# TPA3116AudioAmplifier.net
KiCad netlist of a schematic drawn in EAGLE
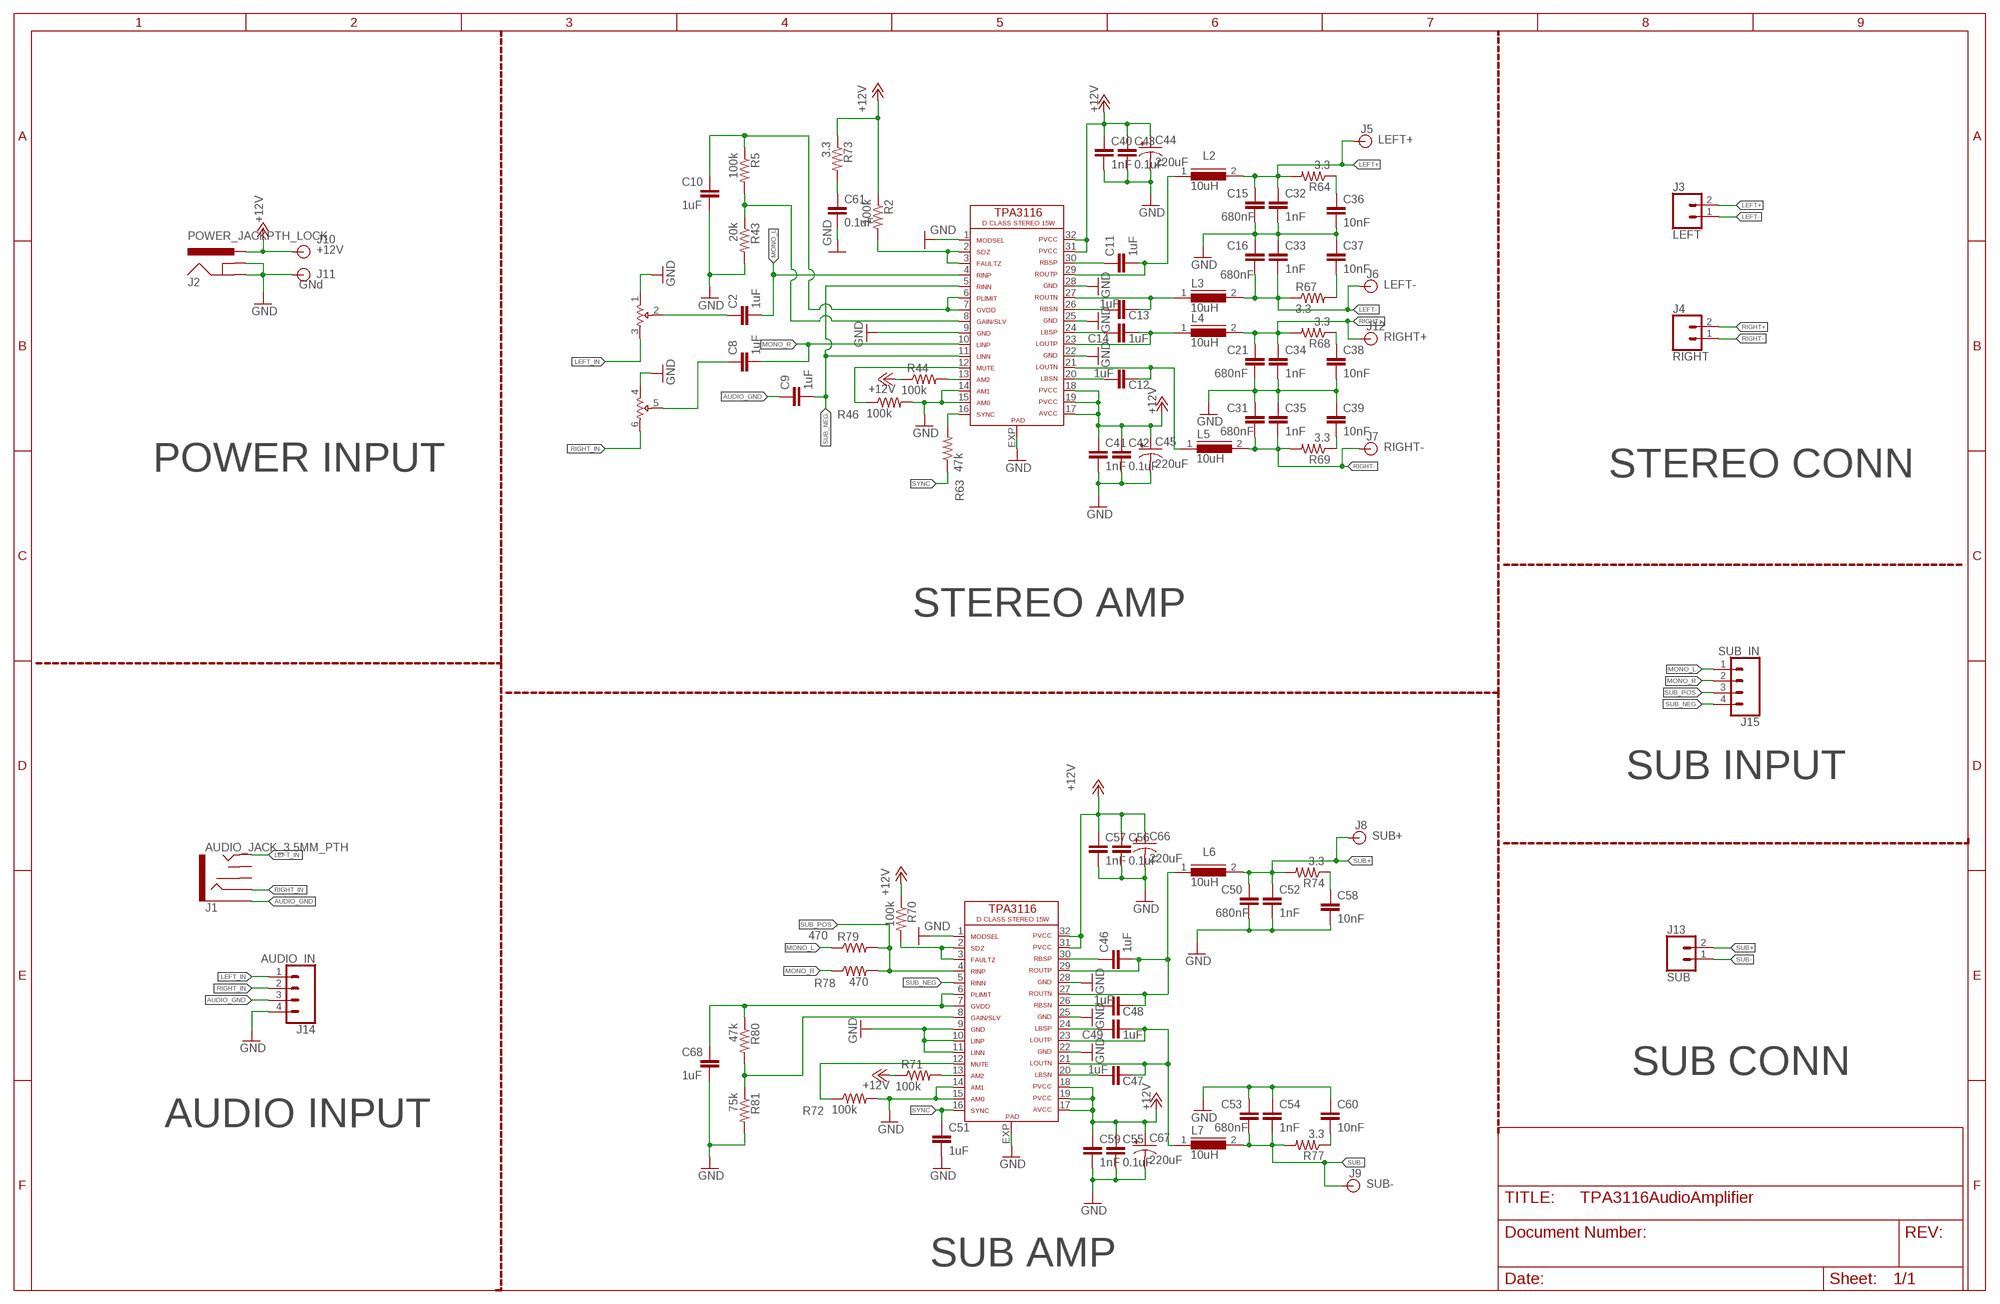
[diagram p0: schematic, sheet 1]

(export (version "E")
  (design (tool "Eeschema 10.0.6"))
  (components
    (comp (ref "C2")
      (value "1uF")
      (footprint "eagle-import:C0603K")
      (libsource (lib "eagle-import") (part "C-EUC0603K"))
    )
    (comp (ref "C8")
      (value "1uF")
      (footprint "eagle-import:C0603K")
      (libsource (lib "eagle-import") (part "C-EUC0603K"))
    )
    (comp (ref "C9")
      (value "1uF")
      (footprint "eagle-import:C0603K")
      (libsource (lib "eagle-import") (part "C-EUC0603K"))
    )
    (comp (ref "C10")
      (value "1uF")
      (footprint "eagle-import:C0603K")
      (libsource (lib "eagle-import") (part "C-EUC0603K"))
    )
    (comp (ref "C11")
      (value "1uF")
      (footprint "eagle-import:C0603K")
      (libsource (lib "eagle-import") (part "C-EUC0603K"))
    )
    (comp (ref "C12")
      (value "1uF")
      (footprint "eagle-import:C0603K")
      (libsource (lib "eagle-import") (part "C-EUC0603K"))
    )
    (comp (ref "C13")
      (value "1uF")
      (footprint "eagle-import:C0603K")
      (libsource (lib "eagle-import") (part "C-EUC0603K"))
    )
    (comp (ref "C14")
      (value "1uF")
      (footprint "eagle-import:C0603K")
      (libsource (lib "eagle-import") (part "C-EUC0603K"))
    )
    (comp (ref "C15")
      (value "680nF")
      (footprint "eagle-import:C0805")
      (libsource (lib "eagle-import") (part "C-EUC0805"))
    )
    (comp (ref "C16")
      (value "680nF")
      (footprint "eagle-import:C0805")
      (libsource (lib "eagle-import") (part "C-EUC0805"))
    )
    (comp (ref "C21")
      (value "680nF")
      (footprint "eagle-import:C0805")
      (libsource (lib "eagle-import") (part "C-EUC0805"))
    )
    (comp (ref "C31")
      (value "680nF")
      (footprint "eagle-import:C0805")
      (libsource (lib "eagle-import") (part "C-EUC0805"))
    )
    (comp (ref "C32")
      (value "1nF")
      (footprint "eagle-import:C0603K")
      (libsource (lib "eagle-import") (part "C-EUC0603K"))
    )
    (comp (ref "C33")
      (value "1nF")
      (footprint "eagle-import:C0603K")
      (libsource (lib "eagle-import") (part "C-EUC0603K"))
    )
    (comp (ref "C34")
      (value "1nF")
      (footprint "eagle-import:C0603K")
      (libsource (lib "eagle-import") (part "C-EUC0603K"))
    )
    (comp (ref "C35")
      (value "1nF")
      (footprint "eagle-import:C0603K")
      (libsource (lib "eagle-import") (part "C-EUC0603K"))
    )
    (comp (ref "C36")
      (value "10nF")
      (footprint "eagle-import:C0603K")
      (libsource (lib "eagle-import") (part "C-EUC0603K"))
    )
    (comp (ref "C37")
      (value "10nF")
      (footprint "eagle-import:C0603K")
      (libsource (lib "eagle-import") (part "C-EUC0603K"))
    )
    (comp (ref "C38")
      (value "10nF")
      (footprint "eagle-import:C0603K")
      (libsource (lib "eagle-import") (part "C-EUC0603K"))
    )
    (comp (ref "C39")
      (value "10nF")
      (footprint "eagle-import:C0603K")
      (libsource (lib "eagle-import") (part "C-EUC0603K"))
    )
    (comp (ref "C40")
      (value "1nF")
      (footprint "eagle-import:C0603K")
      (libsource (lib "eagle-import") (part "C-EUC0603K"))
    )
    (comp (ref "C41")
      (value "1nF")
      (footprint "eagle-import:C0603K")
      (libsource (lib "eagle-import") (part "C-EUC0603K"))
    )
    (comp (ref "C42")
      (value "0.1uF")
      (footprint "eagle-import:C0603K")
      (libsource (lib "eagle-import") (part "C-EUC0603K"))
    )
    (comp (ref "C43")
      (value "0.1uF")
      (footprint "eagle-import:C0603K")
      (libsource (lib "eagle-import") (part "C-EUC0603K"))
    )
    (comp (ref "C44")
      (value "220uF")
      (footprint "eagle-import:E5-10,5")
      (libsource (lib "eagle-import") (part "CPOL-USE5-10.5"))
    )
    (comp (ref "C45")
      (value "220uF")
      (footprint "eagle-import:E5-10,5")
      (libsource (lib "eagle-import") (part "CPOL-USE5-10.5"))
    )
    (comp (ref "C46")
      (value "1uF")
      (footprint "eagle-import:C0603K")
      (libsource (lib "eagle-import") (part "C-EUC0603K"))
    )
    (comp (ref "C47")
      (value "1uF")
      (footprint "eagle-import:C0603K")
      (libsource (lib "eagle-import") (part "C-EUC0603K"))
    )
    (comp (ref "C48")
      (value "1uF")
      (footprint "eagle-import:C0603K")
      (libsource (lib "eagle-import") (part "C-EUC0603K"))
    )
    (comp (ref "C49")
      (value "1uF")
      (footprint "eagle-import:C0603K")
      (libsource (lib "eagle-import") (part "C-EUC0603K"))
    )
    (comp (ref "C50")
      (value "680nF")
      (footprint "eagle-import:C0805")
      (libsource (lib "eagle-import") (part "C-EUC0805"))
    )
    (comp (ref "C51")
      (value "1uF")
      (footprint "eagle-import:C0603K")
      (libsource (lib "eagle-import") (part "C-EUC0603K"))
    )
    (comp (ref "C52")
      (value "1nF")
      (footprint "eagle-import:C0603K")
      (libsource (lib "eagle-import") (part "C-EUC0603K"))
    )
    (comp (ref "C53")
      (value "680nF")
      (footprint "eagle-import:C0805")
      (libsource (lib "eagle-import") (part "C-EUC0805"))
    )
    (comp (ref "C54")
      (value "1nF")
      (footprint "eagle-import:C0603K")
      (libsource (lib "eagle-import") (part "C-EUC0603K"))
    )
    (comp (ref "C55")
      (value "0.1uF")
      (footprint "eagle-import:C0603K")
      (libsource (lib "eagle-import") (part "C-EUC0603K"))
    )
    (comp (ref "C56")
      (value "0.1uF")
      (footprint "eagle-import:C0603K")
      (libsource (lib "eagle-import") (part "C-EUC0603K"))
    )
    (comp (ref "C57")
      (value "1nF")
      (footprint "eagle-import:C0603K")
      (libsource (lib "eagle-import") (part "C-EUC0603K"))
    )
    (comp (ref "C58")
      (value "10nF")
      (footprint "eagle-import:C0603K")
      (libsource (lib "eagle-import") (part "C-EUC0603K"))
    )
    (comp (ref "C59")
      (value "1nF")
      (footprint "eagle-import:C0603K")
      (libsource (lib "eagle-import") (part "C-EUC0603K"))
    )
    (comp (ref "C60")
      (value "10nF")
      (footprint "eagle-import:C0603K")
      (libsource (lib "eagle-import") (part "C-EUC0603K"))
    )
    (comp (ref "C61")
      (value "0.1uF")
      (footprint "eagle-import:C0603K")
      (libsource (lib "eagle-import") (part "C-EUC0603K"))
    )
    (comp (ref "C66")
      (value "220uF")
      (footprint "eagle-import:E5-10,5")
      (libsource (lib "eagle-import") (part "CPOL-USE5-10.5"))
    )
    (comp (ref "C67")
      (value "220uF")
      (footprint "eagle-import:E5-10,5")
      (libsource (lib "eagle-import") (part "CPOL-USE5-10.5"))
    )
    (comp (ref "C68")
      (value "1uF")
      (footprint "eagle-import:C0603K")
      (libsource (lib "eagle-import") (part "C-EUC0603K"))
    )
    (comp (ref "J1")
      (value "AUDIO_JACK_3.5MM_PTH")
      (footprint "eagle-import:AUDIO-JACK")
      (libsource (lib "eagle-import") (part "AUDIO_JACK_3.5MM_PTH"))
    )
    (comp (ref "J2")
      (value "POWER_JACKPTH_LOCK")
      (footprint "eagle-import:POWER_JACK_PTH_LOCK")
      (libsource (lib "eagle-import") (part "POWER_JACKPTH_LOCK"))
    )
    (comp (ref "J3")
      (value "LEFT")
      (footprint "eagle-import:SCREWTERMINAL-5MM-2")
      (libsource (lib "eagle-import") (part "CONN_025MM"))
    )
    (comp (ref "J4")
      (value "RIGHT")
      (footprint "eagle-import:SCREWTERMINAL-5MM-2")
      (libsource (lib "eagle-import") (part "CONN_025MM"))
    )
    (comp (ref "J5")
      (value "LEFT+")
      (footprint "eagle-import:BANANA_CONN")
      (libsource (lib "eagle-import") (part "BANANA_CONN"))
    )
    (comp (ref "J6")
      (value "LEFT-")
      (footprint "eagle-import:BANANA_CONN")
      (libsource (lib "eagle-import") (part "BANANA_CONN"))
    )
    (comp (ref "J7")
      (value "RIGHT-")
      (footprint "eagle-import:BANANA_CONN")
      (libsource (lib "eagle-import") (part "BANANA_CONN"))
    )
    (comp (ref "J8")
      (value "SUB+")
      (footprint "eagle-import:BANANA_CONN")
      (libsource (lib "eagle-import") (part "BANANA_CONN"))
    )
    (comp (ref "J9")
      (value "SUB-")
      (footprint "eagle-import:BANANA_CONN")
      (libsource (lib "eagle-import") (part "BANANA_CONN"))
    )
    (comp (ref "J10")
      (value "+12V")
      (footprint "eagle-import:BANANA_CONN")
      (libsource (lib "eagle-import") (part "BANANA_CONN"))
    )
    (comp (ref "J11")
      (value "GNd")
      (footprint "eagle-import:BANANA_CONN")
      (libsource (lib "eagle-import") (part "BANANA_CONN"))
    )
    (comp (ref "J12")
      (value "RIGHT+")
      (footprint "eagle-import:BANANA_CONN")
      (libsource (lib "eagle-import") (part "BANANA_CONN"))
    )
    (comp (ref "J13")
      (value "SUB")
      (footprint "eagle-import:SCREWTERMINAL-5MM-2")
      (libsource (lib "eagle-import") (part "CONN_025MM"))
    )
    (comp (ref "J14")
      (value "AUDIO_IN")
      (footprint "eagle-import:1X04")
      (libsource (lib "eagle-import") (part "CONN_04"))
    )
    (comp (ref "J15")
      (value "SUB_IN")
      (footprint "eagle-import:1X04")
      (libsource (lib "eagle-import") (part "CONN_04"))
    )
    (comp (ref "L2")
      (value "10uH")
      (footprint "eagle-import:DR125")
      (libsource (lib "eagle-import") (part "DR125"))
    )
    (comp (ref "L3")
      (value "10uH")
      (footprint "eagle-import:DR125")
      (libsource (lib "eagle-import") (part "DR125"))
    )
    (comp (ref "L4")
      (value "10uH")
      (footprint "eagle-import:DR125")
      (libsource (lib "eagle-import") (part "DR125"))
    )
    (comp (ref "L5")
      (value "10uH")
      (footprint "eagle-import:DR125")
      (libsource (lib "eagle-import") (part "DR125"))
    )
    (comp (ref "L6")
      (value "10uH")
      (footprint "eagle-import:DR125")
      (libsource (lib "eagle-import") (part "DR125"))
    )
    (comp (ref "L7")
      (value "10uH")
      (footprint "eagle-import:DR125")
      (libsource (lib "eagle-import") (part "DR125"))
    )
    (comp (ref "R2")
      (value "100k")
      (footprint "eagle-import:R0805")
      (libsource (lib "eagle-import") (part "R-US_R0805"))
    )
    (comp (ref "R5")
      (value "100k")
      (footprint "eagle-import:R0805")
      (libsource (lib "eagle-import") (part "R-US_R0805"))
    )
    (comp (ref "R43")
      (value "20k")
      (footprint "eagle-import:R0805")
      (libsource (lib "eagle-import") (part "R-US_R0805"))
    )
    (comp (ref "R44")
      (value "100k")
      (footprint "eagle-import:R0805")
      (libsource (lib "eagle-import") (part "R-US_R0805"))
    )
    (comp (ref "R46")
      (value "100k")
      (footprint "eagle-import:R0805")
      (libsource (lib "eagle-import") (part "R-US_R0805"))
    )
    (comp (ref "R63")
      (value "47k")
      (footprint "eagle-import:R0805")
      (libsource (lib "eagle-import") (part "R-US_R0805"))
    )
    (comp (ref "R64")
      (value "3.3")
      (footprint "eagle-import:M0805")
      (libsource (lib "eagle-import") (part "R-US_M0805"))
    )
    (comp (ref "R67")
      (value "3.3")
      (footprint "eagle-import:M0805")
      (libsource (lib "eagle-import") (part "R-US_M0805"))
    )
    (comp (ref "R68")
      (value "3.3")
      (footprint "eagle-import:M0805")
      (libsource (lib "eagle-import") (part "R-US_M0805"))
    )
    (comp (ref "R69")
      (value "3.3")
      (footprint "eagle-import:M0805")
      (libsource (lib "eagle-import") (part "R-US_M0805"))
    )
    (comp (ref "R70")
      (value "100k")
      (footprint "eagle-import:R0805")
      (libsource (lib "eagle-import") (part "R-US_R0805"))
    )
    (comp (ref "R71")
      (value "100k")
      (footprint "eagle-import:R0805")
      (libsource (lib "eagle-import") (part "R-US_R0805"))
    )
    (comp (ref "R72")
      (value "100k")
      (footprint "eagle-import:R0805")
      (libsource (lib "eagle-import") (part "R-US_R0805"))
    )
    (comp (ref "R73")
      (value "3.3")
      (footprint "eagle-import:M0805")
      (libsource (lib "eagle-import") (part "R-US_M0805"))
    )
    (comp (ref "R74")
      (value "3.3")
      (footprint "eagle-import:M0805")
      (libsource (lib "eagle-import") (part "R-US_M0805"))
    )
    (comp (ref "R77")
      (value "3.3")
      (footprint "eagle-import:M0805")
      (libsource (lib "eagle-import") (part "R-US_M0805"))
    )
    (comp (ref "R78")
      (value "470")
      (footprint "eagle-import:R0805")
      (libsource (lib "eagle-import") (part "R-US_R0805"))
    )
    (comp (ref "R79")
      (value "470")
      (footprint "eagle-import:R0805")
      (libsource (lib "eagle-import") (part "R-US_R0805"))
    )
    (comp (ref "R80")
      (value "47k")
      (footprint "eagle-import:R0805")
      (libsource (lib "eagle-import") (part "R-US_R0805"))
    )
    (comp (ref "R81")
      (value "75k")
      (footprint "eagle-import:R0805")
      (libsource (lib "eagle-import") (part "R-US_R0805"))
    )
    (comp (ref "U$1")
      (value "TPA3116HTSSOP32")
      (footprint "eagle-import:HTSSOP32DAP")
      (libsource (lib "eagle-import") (part "TPA3116HTSSOP32"))
    )
    (comp (ref "U$2")
      (value "DUAL_POT_H")
      (footprint "eagle-import:DUAL_POT_H")
      (libsource (lib "eagle-import") (part "DUAL_POT_H"))
    )
    (comp (ref "U$3")
      (value "TPA3116HTSSOP32")
      (footprint "eagle-import:HTSSOP32DAP")
      (libsource (lib "eagle-import") (part "TPA3116HTSSOP32"))
    )
  )
  (nets
    (net (code "1") (name "+12V") (class "Default")
      (node (ref "C40") (pin "1") (pinfunction "1_1") (pintype "passive"))
      (node (ref "C41") (pin "1") (pinfunction "1_1") (pintype "passive"))
      (node (ref "C42") (pin "1") (pinfunction "1_1") (pintype "passive"))
      (node (ref "C43") (pin "1") (pinfunction "1_1") (pintype "passive"))
      (node (ref "C44") (pin "+") (pinfunction "+_+") (pintype "passive"))
      (node (ref "C45") (pin "+") (pinfunction "+_+") (pintype "passive"))
      (node (ref "C55") (pin "1") (pinfunction "1_1") (pintype "passive"))
      (node (ref "C56") (pin "1") (pinfunction "1_1") (pintype "passive"))
      (node (ref "C57") (pin "1") (pinfunction "1_1") (pintype "passive"))
      (node (ref "C59") (pin "1") (pinfunction "1_1") (pintype "passive"))
      (node (ref "C66") (pin "+") (pinfunction "+_+") (pintype "passive"))
      (node (ref "C67") (pin "+") (pinfunction "+_+") (pintype "passive"))
      (node (ref "J10") (pin "P$1") (pinfunction "1_P$1") (pintype "passive"))
      (node (ref "J2") (pin "PWR") (pinfunction "PWR_PWR") (pintype "bidirectional"))
      (node (ref "R2") (pin "1") (pinfunction "1_1") (pintype "passive"))
      (node (ref "R44") (pin "1") (pinfunction "1_1") (pintype "passive"))
      (node (ref "R70") (pin "1") (pinfunction "1_1") (pintype "passive"))
      (node (ref "R71") (pin "1") (pinfunction "1_1") (pintype "passive"))
      (node (ref "R73") (pin "1") (pinfunction "1_1") (pintype "passive"))
      (node (ref "U$1") (pin "17") (pinfunction "AVCC_17") (pintype "bidirectional"))
      (node (ref "U$1") (pin "18") (pinfunction "PVCC0_18") (pintype "bidirectional"))
      (node (ref "U$1") (pin "19") (pinfunction "PVCC1_19") (pintype "bidirectional"))
      (node (ref "U$1") (pin "31") (pinfunction "PVCC2_31") (pintype "bidirectional"))
      (node (ref "U$1") (pin "32") (pinfunction "PVCC3_32") (pintype "bidirectional"))
      (node (ref "U$3") (pin "17") (pinfunction "AVCC_17") (pintype "bidirectional"))
      (node (ref "U$3") (pin "18") (pinfunction "PVCC0_18") (pintype "bidirectional"))
      (node (ref "U$3") (pin "19") (pinfunction "PVCC1_19") (pintype "bidirectional"))
      (node (ref "U$3") (pin "31") (pinfunction "PVCC2_31") (pintype "bidirectional"))
      (node (ref "U$3") (pin "32") (pinfunction "PVCC3_32") (pintype "bidirectional"))
    )
    (net (code "2") (name "AUDIO_GND") (class "Default")
      (node (ref "C9") (pin "1") (pinfunction "1_1") (pintype "passive"))
      (node (ref "J1") (pin "SLEEVE") (pinfunction "SLEEVE_SLEEVE") (pintype "bidirectional"))
      (node (ref "J14") (pin "3") (pinfunction "3_3") (pintype "passive"))
    )
    (net (code "3") (name "GND") (class "Default")
      (node (ref "C10") (pin "2") (pinfunction "2_2") (pintype "passive"))
      (node (ref "C15") (pin "2") (pinfunction "2_2") (pintype "passive"))
      (node (ref "C16") (pin "1") (pinfunction "1_1") (pintype "passive"))
      (node (ref "C21") (pin "2") (pinfunction "2_2") (pintype "passive"))
      (node (ref "C31") (pin "1") (pinfunction "1_1") (pintype "passive"))
      (node (ref "C32") (pin "2") (pinfunction "2_2") (pintype "passive"))
      (node (ref "C33") (pin "1") (pinfunction "1_1") (pintype "passive"))
      (node (ref "C34") (pin "2") (pinfunction "2_2") (pintype "passive"))
      (node (ref "C35") (pin "1") (pinfunction "1_1") (pintype "passive"))
      (node (ref "C36") (pin "2") (pinfunction "2_2") (pintype "passive"))
      (node (ref "C37") (pin "1") (pinfunction "1_1") (pintype "passive"))
      (node (ref "C38") (pin "2") (pinfunction "2_2") (pintype "passive"))
      (node (ref "C39") (pin "1") (pinfunction "1_1") (pintype "passive"))
      (node (ref "C40") (pin "2") (pinfunction "2_2") (pintype "passive"))
      (node (ref "C41") (pin "2") (pinfunction "2_2") (pintype "passive"))
      (node (ref "C42") (pin "2") (pinfunction "2_2") (pintype "passive"))
      (node (ref "C43") (pin "2") (pinfunction "2_2") (pintype "passive"))
      (node (ref "C44") (pin "-") (pinfunction "-_-") (pintype "passive"))
      (node (ref "C45") (pin "-") (pinfunction "-_-") (pintype "passive"))
      (node (ref "C50") (pin "2") (pinfunction "2_2") (pintype "passive"))
      (node (ref "C51") (pin "2") (pinfunction "2_2") (pintype "passive"))
      (node (ref "C52") (pin "2") (pinfunction "2_2") (pintype "passive"))
      (node (ref "C53") (pin "1") (pinfunction "1_1") (pintype "passive"))
      (node (ref "C54") (pin "1") (pinfunction "1_1") (pintype "passive"))
      (node (ref "C55") (pin "2") (pinfunction "2_2") (pintype "passive"))
      (node (ref "C56") (pin "2") (pinfunction "2_2") (pintype "passive"))
      (node (ref "C57") (pin "2") (pinfunction "2_2") (pintype "passive"))
      (node (ref "C58") (pin "2") (pinfunction "2_2") (pintype "passive"))
      (node (ref "C59") (pin "2") (pinfunction "2_2") (pintype "passive"))
      (node (ref "C60") (pin "1") (pinfunction "1_1") (pintype "passive"))
      (node (ref "C61") (pin "2") (pinfunction "2_2") (pintype "passive"))
      (node (ref "C66") (pin "-") (pinfunction "-_-") (pintype "passive"))
      (node (ref "C67") (pin "-") (pinfunction "-_-") (pintype "passive"))
      (node (ref "C68") (pin "2") (pinfunction "2_2") (pintype "passive"))
      (node (ref "J11") (pin "P$1") (pinfunction "1_P$1") (pintype "passive"))
      (node (ref "J14") (pin "4") (pinfunction "4_4") (pintype "passive"))
      (node (ref "J2") (pin "GND") (pinfunction "GND_GND") (pintype "bidirectional"))
      (node (ref "J2") (pin "GNDBREAK") (pinfunction "GNDBREAK_GNDBREAK") (pintype "bidirectional"))
      (node (ref "R43") (pin "2") (pinfunction "2_2") (pintype "passive"))
      (node (ref "R46") (pin "2") (pinfunction "2_2") (pintype "passive"))
      (node (ref "R72") (pin "2") (pinfunction "2_2") (pintype "passive"))
      (node (ref "R81") (pin "2") (pinfunction "2_2") (pintype "passive"))
      (node (ref "U$1") (pin "1") (pinfunction "MODSEL_1") (pintype "bidirectional"))
      (node (ref "U$1") (pin "10") (pinfunction "LINP_10") (pintype "bidirectional"))
      (node (ref "U$1") (pin "11") (pinfunction "LINN_11") (pintype "bidirectional"))
      (node (ref "U$1") (pin "14") (pinfunction "AM1_14") (pintype "bidirectional"))
      (node (ref "U$1") (pin "15") (pinfunction "AM0_15") (pintype "bidirectional"))
      (node (ref "U$1") (pin "22") (pinfunction "GND1_22") (pintype "bidirectional"))
      (node (ref "U$1") (pin "25") (pinfunction "GND2_25") (pintype "bidirectional"))
      (node (ref "U$1") (pin "28") (pinfunction "GND3_28") (pintype "bidirectional"))
      (node (ref "U$1") (pin "9") (pinfunction "GND0_9") (pintype "bidirectional"))
      (node (ref "U$1") (pin "EXP") (pinfunction "EXP_EXP") (pintype "bidirectional"))
      (node (ref "U$2") (pin "1") (pinfunction "1_1") (pintype "bidirectional"))
      (node (ref "U$2") (pin "4") (pinfunction "4_4") (pintype "bidirectional"))
      (node (ref "U$3") (pin "1") (pinfunction "MODSEL_1") (pintype "bidirectional"))
      (node (ref "U$3") (pin "14") (pinfunction "AM1_14") (pintype "bidirectional"))
      (node (ref "U$3") (pin "15") (pinfunction "AM0_15") (pintype "bidirectional"))
      (node (ref "U$3") (pin "22") (pinfunction "GND1_22") (pintype "bidirectional"))
      (node (ref "U$3") (pin "25") (pinfunction "GND2_25") (pintype "bidirectional"))
      (node (ref "U$3") (pin "28") (pinfunction "GND3_28") (pintype "bidirectional"))
      (node (ref "U$3") (pin "9") (pinfunction "GND0_9") (pintype "bidirectional"))
      (node (ref "U$3") (pin "EXP") (pinfunction "EXP_EXP") (pintype "bidirectional"))
    )
    (net (code "4") (name "LEFT+") (class "Default")
      (node (ref "C15") (pin "1") (pinfunction "1_1") (pintype "passive"))
      (node (ref "C32") (pin "1") (pinfunction "1_1") (pintype "passive"))
      (node (ref "J3") (pin "2") (pinfunction "2_2") (pintype "passive"))
      (node (ref "J5") (pin "P$1") (pinfunction "1_P$1") (pintype "passive"))
      (node (ref "L2") (pin "2") (pinfunction "2_2") (pintype "passive"))
      (node (ref "R64") (pin "2") (pinfunction "2_2") (pintype "passive"))
    )
    (net (code "5") (name "LEFT-") (class "Default")
      (node (ref "C16") (pin "2") (pinfunction "2_2") (pintype "passive"))
      (node (ref "C33") (pin "2") (pinfunction "2_2") (pintype "passive"))
      (node (ref "J3") (pin "1") (pinfunction "1_1") (pintype "passive"))
      (node (ref "J6") (pin "P$1") (pinfunction "1_P$1") (pintype "passive"))
      (node (ref "L3") (pin "2") (pinfunction "2_2") (pintype "passive"))
      (node (ref "R67") (pin "1") (pinfunction "1_1") (pintype "passive"))
    )
    (net (code "6") (name "LEFT_IN") (class "Default")
      (node (ref "J1") (pin "TIP") (pinfunction "TIP_TIP") (pintype "bidirectional"))
      (node (ref "J14") (pin "1") (pinfunction "1_1") (pintype "passive"))
      (node (ref "U$2") (pin "3") (pinfunction "3_3") (pintype "bidirectional"))
    )
    (net (code "7") (name "MONO_L") (class "Default")
      (node (ref "C2") (pin "2") (pinfunction "2_2") (pintype "passive"))
      (node (ref "J15") (pin "1") (pinfunction "1_1") (pintype "passive"))
      (node (ref "R79") (pin "1") (pinfunction "1_1") (pintype "passive"))
      (node (ref "U$3") (pin "4") (pinfunction "RINP_4") (pintype "bidirectional"))
    )
    (net (code "8") (name "MONO_R") (class "Default")
      (node (ref "C8") (pin "2") (pinfunction "2_2") (pintype "passive"))
      (node (ref "J15") (pin "2") (pinfunction "2_2") (pintype "passive"))
      (node (ref "R78") (pin "1") (pinfunction "1_1") (pintype "passive"))
      (node (ref "U$3") (pin "10") (pinfunction "LINP_10") (pintype "bidirectional"))
    )
    (net (code "9") (name "Net-(C2-Pad1)") (class "Default")
      (node (ref "C2") (pin "1") (pinfunction "1_1") (pintype "passive"))
      (node (ref "U$2") (pin "2") (pinfunction "2_2") (pintype "bidirectional"))
    )
    (net (code "10") (name "Net-(C8-Pad1)") (class "Default")
      (node (ref "C8") (pin "1") (pinfunction "1_1") (pintype "passive"))
      (node (ref "U$2") (pin "5") (pinfunction "5_5") (pintype "bidirectional"))
    )
    (net (code "11") (name "Net-(C36-Pad1)") (class "Default")
      (node (ref "C36") (pin "1") (pinfunction "1_1") (pintype "passive"))
      (node (ref "R64") (pin "1") (pinfunction "1_1") (pintype "passive"))
    )
    (net (code "12") (name "Net-(C37-Pad2)") (class "Default")
      (node (ref "C37") (pin "2") (pinfunction "2_2") (pintype "passive"))
      (node (ref "R67") (pin "2") (pinfunction "2_2") (pintype "passive"))
    )
    (net (code "13") (name "Net-(C38-Pad1)") (class "Default")
      (node (ref "C38") (pin "1") (pinfunction "1_1") (pintype "passive"))
      (node (ref "R68") (pin "1") (pinfunction "1_1") (pintype "passive"))
    )
    (net (code "14") (name "Net-(C39-Pad2)") (class "Default")
      (node (ref "C39") (pin "2") (pinfunction "2_2") (pintype "passive"))
      (node (ref "R69") (pin "1") (pinfunction "1_1") (pintype "passive"))
    )
    (net (code "15") (name "Net-(C58-Pad1)") (class "Default")
      (node (ref "C58") (pin "1") (pinfunction "1_1") (pintype "passive"))
      (node (ref "R74") (pin "1") (pinfunction "1_1") (pintype "passive"))
    )
    (net (code "16") (name "Net-(C60-Pad2)") (class "Default")
      (node (ref "C60") (pin "2") (pinfunction "2_2") (pintype "passive"))
      (node (ref "R77") (pin "1") (pinfunction "1_1") (pintype "passive"))
    )
    (net (code "17") (name "Net-(C61-Pad1)") (class "Default")
      (node (ref "C61") (pin "1") (pinfunction "1_1") (pintype "passive"))
      (node (ref "R73") (pin "2") (pinfunction "2_2") (pintype "passive"))
    )
    (net (code "18") (name "Net-(U$1-AM2)") (class "Default")
      (node (ref "R71") (pin "2") (pinfunction "2_2") (pintype "passive"))
      (node (ref "U$1") (pin "13") (pinfunction "AM2_13") (pintype "bidirectional"))
    )
    (net (code "19") (name "Net-(U$1-FAULTZ)") (class "Default")
      (node (ref "R70") (pin "2") (pinfunction "2_2") (pintype "passive"))
      (node (ref "U$1") (pin "2") (pinfunction "SDZ_2") (pintype "bidirectional"))
      (node (ref "U$1") (pin "3") (pinfunction "FAULTZ_3") (pintype "bidirectional"))
    )
    (net (code "20") (name "Net-(U$1-GAIN{slash}SLV)") (class "Default")
      (node (ref "R80") (pin "2") (pinfunction "2_2") (pintype "passive"))
      (node (ref "R81") (pin "1") (pinfunction "1_1") (pintype "passive"))
      (node (ref "U$1") (pin "8") (pinfunction "GAIN/SLV_8") (pintype "bidirectional"))
    )
    (net (code "21") (name "Net-(U$1-GVDD)") (class "Default")
      (node (ref "C68") (pin "1") (pinfunction "1_1") (pintype "passive"))
      (node (ref "R80") (pin "1") (pinfunction "1_1") (pintype "passive"))
      (node (ref "U$1") (pin "6") (pinfunction "PLIMIT_6") (pintype "bidirectional"))
      (node (ref "U$1") (pin "7") (pinfunction "GVDD_7") (pintype "bidirectional"))
    )
    (net (code "22") (name "Net-(U$1-LBSN)") (class "Default")
      (node (ref "C47") (pin "1") (pinfunction "1_1") (pintype "passive"))
      (node (ref "U$1") (pin "20") (pinfunction "LBSN_20") (pintype "bidirectional"))
    )
    (net (code "23") (name "Net-(U$1-LBSP)") (class "Default")
      (node (ref "C49") (pin "1") (pinfunction "1_1") (pintype "passive"))
      (node (ref "U$1") (pin "24") (pinfunction "LBSP_24") (pintype "bidirectional"))
    )
    (net (code "24") (name "Net-(U$1-LOUTN)") (class "Default")
      (node (ref "C47") (pin "2") (pinfunction "2_2") (pintype "passive"))
      (node (ref "C49") (pin "2") (pinfunction "2_2") (pintype "passive"))
      (node (ref "L7") (pin "1") (pinfunction "1_1") (pintype "passive"))
      (node (ref "U$1") (pin "21") (pinfunction "LOUTN_21") (pintype "bidirectional"))
      (node (ref "U$1") (pin "23") (pinfunction "OUTPL_23") (pintype "bidirectional"))
    )
    (net (code "25") (name "Net-(U$1-MUTE)") (class "Default")
      (node (ref "R72") (pin "1") (pinfunction "1_1") (pintype "passive"))
      (node (ref "U$1") (pin "12") (pinfunction "MUTE_12") (pintype "bidirectional"))
    )
    (net (code "26") (name "Net-(U$1-RBSN)") (class "Default")
      (node (ref "C48") (pin "1") (pinfunction "1_1") (pintype "passive"))
      (node (ref "U$1") (pin "26") (pinfunction "RBSN_26") (pintype "bidirectional"))
    )
    (net (code "27") (name "Net-(U$1-RBSP)") (class "Default")
      (node (ref "C46") (pin "1") (pinfunction "1_1") (pintype "passive"))
      (node (ref "U$1") (pin "30") (pinfunction "RBSP_30") (pintype "bidirectional"))
    )
    (net (code "28") (name "Net-(U$1-ROUTN)") (class "Default")
      (node (ref "C46") (pin "2") (pinfunction "2_2") (pintype "passive"))
      (node (ref "C48") (pin "2") (pinfunction "2_2") (pintype "passive"))
      (node (ref "L6") (pin "1") (pinfunction "1_1") (pintype "passive"))
      (node (ref "U$1") (pin "27") (pinfunction "ROUTN_27") (pintype "bidirectional"))
      (node (ref "U$1") (pin "29") (pinfunction "ROUTP_29") (pintype "bidirectional"))
    )
    (net (code "29") (name "Net-(U$3-AM2)") (class "Default")
      (node (ref "R44") (pin "2") (pinfunction "2_2") (pintype "passive"))
      (node (ref "U$3") (pin "13") (pinfunction "AM2_13") (pintype "bidirectional"))
    )
    (net (code "30") (name "Net-(U$3-FAULTZ)") (class "Default")
      (node (ref "R2") (pin "2") (pinfunction "2_2") (pintype "passive"))
      (node (ref "U$3") (pin "2") (pinfunction "SDZ_2") (pintype "bidirectional"))
      (node (ref "U$3") (pin "3") (pinfunction "FAULTZ_3") (pintype "bidirectional"))
    )
    (net (code "31") (name "Net-(U$3-GAIN{slash}SLV)") (class "Default")
      (node (ref "R43") (pin "1") (pinfunction "1_1") (pintype "passive"))
      (node (ref "R5") (pin "2") (pinfunction "2_2") (pintype "passive"))
      (node (ref "U$3") (pin "8") (pinfunction "GAIN/SLV_8") (pintype "bidirectional"))
    )
    (net (code "32") (name "Net-(U$3-GVDD)") (class "Default")
      (node (ref "C10") (pin "1") (pinfunction "1_1") (pintype "passive"))
      (node (ref "R5") (pin "1") (pinfunction "1_1") (pintype "passive"))
      (node (ref "U$3") (pin "6") (pinfunction "PLIMIT_6") (pintype "bidirectional"))
      (node (ref "U$3") (pin "7") (pinfunction "GVDD_7") (pintype "bidirectional"))
    )
    (net (code "33") (name "Net-(U$3-LBSN)") (class "Default")
      (node (ref "C12") (pin "1") (pinfunction "1_1") (pintype "passive"))
      (node (ref "U$3") (pin "20") (pinfunction "LBSN_20") (pintype "bidirectional"))
    )
    (net (code "34") (name "Net-(U$3-LBSP)") (class "Default")
      (node (ref "C14") (pin "1") (pinfunction "1_1") (pintype "passive"))
      (node (ref "U$3") (pin "24") (pinfunction "LBSP_24") (pintype "bidirectional"))
    )
    (net (code "35") (name "Net-(U$3-LOUTN)") (class "Default")
      (node (ref "C12") (pin "2") (pinfunction "2_2") (pintype "passive"))
      (node (ref "L5") (pin "1") (pinfunction "1_1") (pintype "passive"))
      (node (ref "U$3") (pin "21") (pinfunction "LOUTN_21") (pintype "bidirectional"))
    )
    (net (code "36") (name "Net-(U$3-MUTE)") (class "Default")
      (node (ref "R46") (pin "1") (pinfunction "1_1") (pintype "passive"))
      (node (ref "U$3") (pin "12") (pinfunction "MUTE_12") (pintype "bidirectional"))
    )
    (net (code "37") (name "Net-(U$3-OUTPL)") (class "Default")
      (node (ref "C14") (pin "2") (pinfunction "2_2") (pintype "passive"))
      (node (ref "L4") (pin "1") (pinfunction "1_1") (pintype "passive"))
      (node (ref "U$3") (pin "23") (pinfunction "OUTPL_23") (pintype "bidirectional"))
    )
    (net (code "38") (name "Net-(U$3-RBSN)") (class "Default")
      (node (ref "C13") (pin "1") (pinfunction "1_1") (pintype "passive"))
      (node (ref "U$3") (pin "26") (pinfunction "RBSN_26") (pintype "bidirectional"))
    )
    (net (code "39") (name "Net-(U$3-RBSP)") (class "Default")
      (node (ref "C11") (pin "1") (pinfunction "1_1") (pintype "passive"))
      (node (ref "U$3") (pin "30") (pinfunction "RBSP_30") (pintype "bidirectional"))
    )
    (net (code "40") (name "Net-(U$3-ROUTN)") (class "Default")
      (node (ref "C13") (pin "2") (pinfunction "2_2") (pintype "passive"))
      (node (ref "L3") (pin "1") (pinfunction "1_1") (pintype "passive"))
      (node (ref "U$3") (pin "27") (pinfunction "ROUTN_27") (pintype "bidirectional"))
    )
    (net (code "41") (name "Net-(U$3-ROUTP)") (class "Default")
      (node (ref "C11") (pin "2") (pinfunction "2_2") (pintype "passive"))
      (node (ref "L2") (pin "1") (pinfunction "1_1") (pintype "passive"))
      (node (ref "U$3") (pin "29") (pinfunction "ROUTP_29") (pintype "bidirectional"))
    )
    (net (code "42") (name "Net-(U$3-SYNC)") (class "Default")
      (node (ref "R63") (pin "2") (pinfunction "2_2") (pintype "passive"))
      (node (ref "U$3") (pin "16") (pinfunction "SYNC_16") (pintype "bidirectional"))
    )
    (net (code "43") (name "RIGHT+") (class "Default")
      (node (ref "C21") (pin "1") (pinfunction "1_1") (pintype "passive"))
      (node (ref "C34") (pin "1") (pinfunction "1_1") (pintype "passive"))
      (node (ref "J12") (pin "P$1") (pinfunction "1_P$1") (pintype "passive"))
      (node (ref "J4") (pin "2") (pinfunction "2_2") (pintype "passive"))
      (node (ref "L4") (pin "2") (pinfunction "2_2") (pintype "passive"))
      (node (ref "R68") (pin "2") (pinfunction "2_2") (pintype "passive"))
    )
    (net (code "44") (name "RIGHT-") (class "Default")
      (node (ref "C31") (pin "2") (pinfunction "2_2") (pintype "passive"))
      (node (ref "C35") (pin "2") (pinfunction "2_2") (pintype "passive"))
      (node (ref "J4") (pin "1") (pinfunction "1_1") (pintype "passive"))
      (node (ref "J7") (pin "P$1") (pinfunction "1_P$1") (pintype "passive"))
      (node (ref "L5") (pin "2") (pinfunction "2_2") (pintype "passive"))
      (node (ref "R69") (pin "2") (pinfunction "2_2") (pintype "passive"))
    )
    (net (code "45") (name "RIGHT_IN") (class "Default")
      (node (ref "J1") (pin "RING") (pinfunction "RING_RING") (pintype "bidirectional"))
      (node (ref "J14") (pin "2") (pinfunction "2_2") (pintype "passive"))
      (node (ref "U$2") (pin "6") (pinfunction "6_6") (pintype "bidirectional"))
    )
    (net (code "46") (name "SUB+") (class "Default")
      (node (ref "C50") (pin "1") (pinfunction "1_1") (pintype "passive"))
      (node (ref "C52") (pin "1") (pinfunction "1_1") (pintype "passive"))
      (node (ref "J13") (pin "2") (pinfunction "2_2") (pintype "passive"))
      (node (ref "J8") (pin "P$1") (pinfunction "1_P$1") (pintype "passive"))
      (node (ref "L6") (pin "2") (pinfunction "2_2") (pintype "passive"))
      (node (ref "R74") (pin "2") (pinfunction "2_2") (pintype "passive"))
    )
    (net (code "47") (name "SUB-") (class "Default")
      (node (ref "C53") (pin "2") (pinfunction "2_2") (pintype "passive"))
      (node (ref "C54") (pin "2") (pinfunction "2_2") (pintype "passive"))
      (node (ref "J13") (pin "1") (pinfunction "1_1") (pintype "passive"))
      (node (ref "J9") (pin "P$1") (pinfunction "1_P$1") (pintype "passive"))
      (node (ref "L7") (pin "2") (pinfunction "2_2") (pintype "passive"))
      (node (ref "R77") (pin "2") (pinfunction "2_2") (pintype "passive"))
    )
    (net (code "48") (name "SUB_NEG") (class "Default")
      (node (ref "C9") (pin "2") (pinfunction "2_2") (pintype "passive"))
      (node (ref "J15") (pin "4") (pinfunction "4_4") (pintype "passive"))
      (node (ref "U$1") (pin "5") (pinfunction "RINN_5") (pintype "bidirectional"))
      (node (ref "U$3") (pin "11") (pinfunction "LINN_11") (pintype "bidirectional"))
      (node (ref "U$3") (pin "5") (pinfunction "RINN_5") (pintype "bidirectional"))
    )
    (net (code "49") (name "SUB_POS") (class "Default")
      (node (ref "J15") (pin "3") (pinfunction "3_3") (pintype "passive"))
      (node (ref "R78") (pin "2") (pinfunction "2_2") (pintype "passive"))
      (node (ref "R79") (pin "2") (pinfunction "2_2") (pintype "passive"))
      (node (ref "U$1") (pin "4") (pinfunction "RINP_4") (pintype "bidirectional"))
    )
    (net (code "50") (name "SYNC") (class "Default")
      (node (ref "C51") (pin "1") (pinfunction "1_1") (pintype "passive"))
      (node (ref "R63") (pin "1") (pinfunction "1_1") (pintype "passive"))
      (node (ref "U$1") (pin "16") (pinfunction "SYNC_16") (pintype "bidirectional"))
    )
    (net (code "51") (name "unconnected-(J1-PadRSH)") (class "Default")
      (node (ref "J1") (pin "RSH") (pinfunction "RSH_RSH") (pintype "bidirectional"))
    )
    (net (code "52") (name "unconnected-(J1-PadTSH)") (class "Default")
      (node (ref "J1") (pin "TSH") (pinfunction "TSH_TSH") (pintype "bidirectional"))
    )
  )
)
